# Digit_Board.net
KiCad netlist of a schematic drawn in Altium Designer
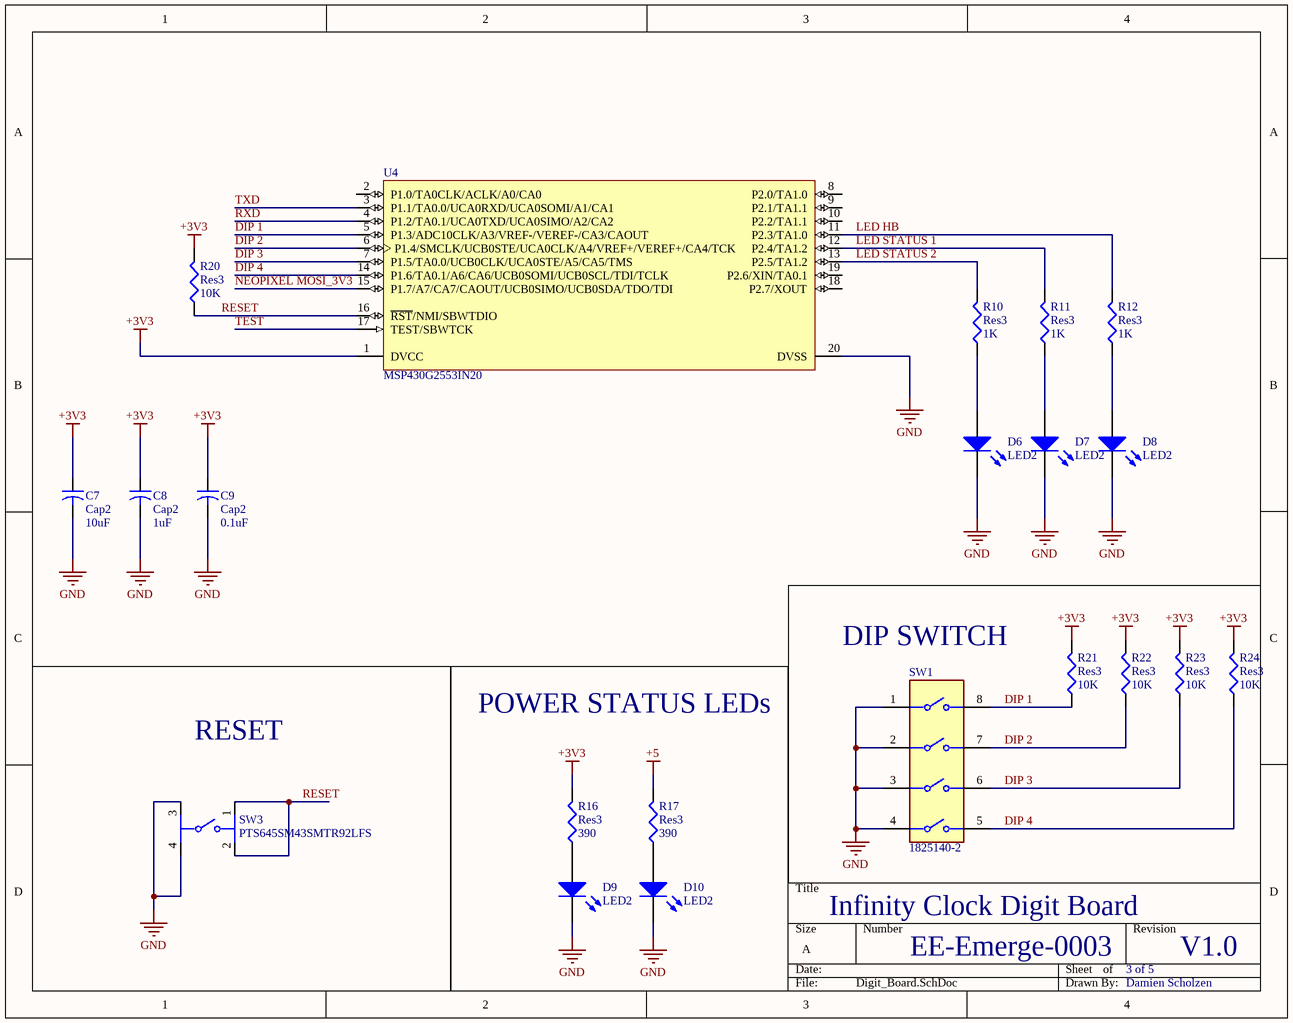
[diagram p0: Digit_Board.SchDoc]

(export (version "E")
  (design (tool "Eeschema 10.0.6"))
  (components
    (comp (ref "C7")
      (value "Cap2")
      (footprint "C0805")
      (description "Capacitor")
      (fields (field (name "ALTIUM_VALUE") "10uF") (field (name "PUBLISHER") "Altium Limited"))
      (libsource (lib "EE_Emerge_SkillsProject (1)") (part "Cap2"))
    )
    (comp (ref "C8")
      (value "Cap2")
      (footprint "C0805")
      (description "Capacitor")
      (fields (field (name "ALTIUM_VALUE") "1uF") (field (name "PUBLISHER") "Altium Limited"))
      (libsource (lib "EE_Emerge_SkillsProject (1)") (part "Cap2_1"))
    )
    (comp (ref "C9")
      (value "Cap2")
      (footprint "C0805")
      (description "Capacitor")
      (fields (field (name "ALTIUM_VALUE") "0.1uF") (field (name "PUBLISHER") "Altium Limited"))
      (libsource (lib "EE_Emerge_SkillsProject (1)") (part "Cap2_2"))
    )
    (comp (ref "D6")
      (value "LED2")
      (footprint "3.2X1.6X1.1")
      (description "Typical RED, GREEN, YELLOW, AMBER GaAs LED")
      (fields (field (name "PUBLISHER") "Altium Limited"))
      (libsource (lib "EE_Emerge_SkillsProject (1)") (part "LED2"))
    )
    (comp (ref "D7")
      (value "LED2")
      (footprint "3.2X1.6X1.1")
      (description "Typical RED, GREEN, YELLOW, AMBER GaAs LED")
      (fields (field (name "PUBLISHER") "Altium Limited"))
      (libsource (lib "EE_Emerge_SkillsProject (1)") (part "LED2"))
    )
    (comp (ref "D8")
      (value "LED2")
      (footprint "3.2X1.6X1.1")
      (description "Typical RED, GREEN, YELLOW, AMBER GaAs LED")
      (fields (field (name "PUBLISHER") "Altium Limited"))
      (libsource (lib "EE_Emerge_SkillsProject (1)") (part "LED2"))
    )
    (comp (ref "D9")
      (value "LED2")
      (footprint "3.2X1.6X1.1")
      (description "Typical RED, GREEN, YELLOW, AMBER GaAs LED")
      (fields (field (name "PUBLISHER") "Altium Limited"))
      (libsource (lib "EE_Emerge_SkillsProject (1)") (part "LED2"))
    )
    (comp (ref "D10")
      (value "LED2")
      (footprint "3.2X1.6X1.1")
      (description "Typical RED, GREEN, YELLOW, AMBER GaAs LED")
      (fields (field (name "PUBLISHER") "Altium Limited"))
      (libsource (lib "EE_Emerge_SkillsProject (1)") (part "LED2"))
    )
    (comp (ref "R10")
      (value "Res3")
      (footprint "6-0805_N")
      (description "Resistor")
      (fields (field (name "ALTIUM_VALUE") "1K") (field (name "PUBLISHER") "Altium Limited"))
      (libsource (lib "EE_Emerge_SkillsProject (1)") (part "Res3_2"))
    )
    (comp (ref "R11")
      (value "Res3")
      (footprint "6-0805_N")
      (description "Resistor")
      (fields (field (name "ALTIUM_VALUE") "1K") (field (name "PUBLISHER") "Altium Limited"))
      (libsource (lib "EE_Emerge_SkillsProject (1)") (part "Res3_2"))
    )
    (comp (ref "R12")
      (value "Res3")
      (footprint "6-0805_N")
      (description "Resistor")
      (fields (field (name "ALTIUM_VALUE") "1K") (field (name "PUBLISHER") "Altium Limited"))
      (libsource (lib "EE_Emerge_SkillsProject (1)") (part "Res3_2"))
    )
    (comp (ref "R16")
      (value "Res3")
      (footprint "6-0805_N")
      (description "Resistor")
      (fields (field (name "ALTIUM_VALUE") "390") (field (name "PUBLISHER") "Altium Limited"))
      (libsource (lib "EE_Emerge_SkillsProject (1)") (part "Res3_4"))
    )
    (comp (ref "R17")
      (value "Res3")
      (footprint "6-0805_N")
      (description "Resistor")
      (fields (field (name "ALTIUM_VALUE") "390") (field (name "PUBLISHER") "Altium Limited"))
      (libsource (lib "EE_Emerge_SkillsProject (1)") (part "Res3_4"))
    )
    (comp (ref "R20")
      (value "Res3")
      (footprint "6-0805_N")
      (description "Resistor")
      (fields (field (name "ALTIUM_VALUE") "10K") (field (name "PUBLISHER") "Altium Limited"))
      (libsource (lib "EE_Emerge_SkillsProject (1)") (part "Res3_3"))
    )
    (comp (ref "R21")
      (value "Res3")
      (footprint "6-0805_N")
      (description "Resistor")
      (fields (field (name "ALTIUM_VALUE") "10K") (field (name "PUBLISHER") "Altium Limited"))
      (libsource (lib "EE_Emerge_SkillsProject (1)") (part "Res3_3"))
    )
    (comp (ref "R22")
      (value "Res3")
      (footprint "6-0805_N")
      (description "Resistor")
      (fields (field (name "ALTIUM_VALUE") "10K") (field (name "PUBLISHER") "Altium Limited"))
      (libsource (lib "EE_Emerge_SkillsProject (1)") (part "Res3_3"))
    )
    (comp (ref "R23")
      (value "Res3")
      (footprint "6-0805_N")
      (description "Resistor")
      (fields (field (name "ALTIUM_VALUE") "10K") (field (name "PUBLISHER") "Altium Limited"))
      (libsource (lib "EE_Emerge_SkillsProject (1)") (part "Res3_3"))
    )
    (comp (ref "R24")
      (value "Res3")
      (footprint "6-0805_N")
      (description "Resistor")
      (fields (field (name "ALTIUM_VALUE") "10K") (field (name "PUBLISHER") "Altium Limited"))
      (libsource (lib "EE_Emerge_SkillsProject (1)") (part "Res3_3"))
    )
    (comp (ref "SW1")
      (value "1825140-2")
      (footprint "FP-1825140-2-MFG")
      (description "SWITCH SLIDE DIP SPST 25MA 24V")
      (libsource (lib "Altium Content Vault") (part "ee767f539d9274548732198086319ae"))
    )
    (comp (ref "SW3")
      (value "PTS645SM43SMTR92LFS")
      (footprint "FP-PTS645SM43SMTR92LFS-MFG")
      (description "SWITCH TACTILE SPST-NO 0.05A 12V")
      (libsource (lib "Altium Content Vault") (part "1adf0dd01260c80cf25a44bfd6b99ba"))
    )
    (comp (ref "U4")
      (value "MSP430G2553IN20")
      (footprint "N0020A")
      (fields (field (name "MANUFACTURER") "Texas Instruments"))
      (libsource (lib "EE_Emerge_SkillsProject (1)") (part "CMP-0365-00184-2"))
    )
  )
  (nets
    (net (code "1") (name "+3V3") (class "Default")
      (node (ref "C7") (pin "1") (pinfunction "1_1") (pintype "passive"))
      (node (ref "C8") (pin "1") (pinfunction "1_1") (pintype "passive"))
      (node (ref "C9") (pin "1") (pinfunction "1_1") (pintype "passive"))
      (node (ref "R16") (pin "2") (pinfunction "2_2") (pintype "passive"))
      (node (ref "R20") (pin "2") (pinfunction "2_2") (pintype "passive"))
      (node (ref "R21") (pin "2") (pinfunction "2_2") (pintype "passive"))
      (node (ref "R22") (pin "2") (pinfunction "2_2") (pintype "passive"))
      (node (ref "R23") (pin "2") (pinfunction "2_2") (pintype "passive"))
      (node (ref "R24") (pin "2") (pinfunction "2_2") (pintype "passive"))
      (node (ref "U4") (pin "1") (pinfunction "DVCC_1") (pintype "power_in"))
    )
    (net (code "2") (name "+5") (class "Default")
      (node (ref "R17") (pin "2") (pinfunction "2_2") (pintype "passive"))
    )
    (net (code "3") (name "/DIP 1") (class "Default")
      (node (ref "R21") (pin "1") (pinfunction "1_1") (pintype "passive"))
      (node (ref "SW1") (pin "8") (pinfunction "8_8") (pintype "passive"))
      (node (ref "U4") (pin "5") (pinfunction "P1.3/ADC10CLK/A3/VREF-/VEREF-/CA3/CAOUT_5") (pintype "bidirectional"))
    )
    (net (code "4") (name "/DIP 2") (class "Default")
      (node (ref "R22") (pin "1") (pinfunction "1_1") (pintype "passive"))
      (node (ref "SW1") (pin "7") (pinfunction "7_7") (pintype "passive"))
      (node (ref "U4") (pin "6") (pinfunction "P1.4/SMCLK/UCB0STE/UCA0CLK/A4/VREF+/VEREF+/CA4/TCK_6") (pintype "bidirectional"))
    )
    (net (code "5") (name "/DIP 3") (class "Default")
      (node (ref "R23") (pin "1") (pinfunction "1_1") (pintype "passive"))
      (node (ref "SW1") (pin "6") (pinfunction "6_6") (pintype "passive"))
      (node (ref "U4") (pin "7") (pinfunction "P1.5/TA0.0/UCB0CLK/UCA0STE/A5/CA5/TMS_7") (pintype "bidirectional"))
    )
    (net (code "6") (name "/DIP 4") (class "Default")
      (node (ref "R24") (pin "1") (pinfunction "1_1") (pintype "passive"))
      (node (ref "SW1") (pin "5") (pinfunction "5_5") (pintype "passive"))
      (node (ref "U4") (pin "14") (pinfunction "P1.6/TA0.1/A6/CA6/UCB0SOMI/UCB0SCL/TDI/TCLK_14") (pintype "bidirectional"))
    )
    (net (code "7") (name "/LED HB") (class "Default")
      (node (ref "R12") (pin "2") (pinfunction "2_2") (pintype "passive"))
      (node (ref "U4") (pin "11") (pinfunction "P2.3/TA1.0_11") (pintype "bidirectional"))
    )
    (net (code "8") (name "/LED STATUS 1") (class "Default")
      (node (ref "R11") (pin "2") (pinfunction "2_2") (pintype "passive"))
      (node (ref "U4") (pin "12") (pinfunction "P2.4/TA1.2_12") (pintype "bidirectional"))
    )
    (net (code "9") (name "/LED STATUS 2") (class "Default")
      (node (ref "R10") (pin "2") (pinfunction "2_2") (pintype "passive"))
      (node (ref "U4") (pin "13") (pinfunction "P2.5/TA1.2_13") (pintype "bidirectional"))
    )
    (net (code "10") (name "/NEOPIXEL MOSI_3V3") (class "Default")
      (node (ref "U4") (pin "15") (pinfunction "P1.7/A7/CA7/CAOUT/UCB0SIMO/UCB0SDA/TDO/TDI_15") (pintype "bidirectional"))
    )
    (net (code "11") (name "/RESET") (class "Default")
      (node (ref "R20") (pin "1") (pinfunction "1_1") (pintype "passive"))
      (node (ref "SW3") (pin "1") (pinfunction "1_1") (pintype "passive"))
      (node (ref "SW3") (pin "2") (pinfunction "2_2") (pintype "passive"))
      (node (ref "U4") (pin "16") (pinfunction "~{RST}/NMI/SBWTDIO_16") (pintype "bidirectional"))
    )
    (net (code "12") (name "/RXD") (class "Default")
      (node (ref "U4") (pin "4") (pinfunction "P1.2/TA0.1/UCA0TXD/UCA0SIMO/A2/CA2_4") (pintype "bidirectional"))
    )
    (net (code "13") (name "/TEST") (class "Default")
      (node (ref "U4") (pin "17") (pinfunction "TEST/SBWTCK_17") (pintype "input"))
    )
    (net (code "14") (name "/TXD") (class "Default")
      (node (ref "U4") (pin "3") (pinfunction "P1.1/TA0.0/UCA0RXD/UCA0SOMI/A1/CA1_3") (pintype "bidirectional"))
    )
    (net (code "15") (name "GND") (class "Default")
      (node (ref "C7") (pin "2") (pinfunction "2_2") (pintype "passive"))
      (node (ref "C8") (pin "2") (pinfunction "2_2") (pintype "passive"))
      (node (ref "C9") (pin "2") (pinfunction "2_2") (pintype "passive"))
      (node (ref "D10") (pin "2") (pinfunction "K_2") (pintype "passive"))
      (node (ref "D6") (pin "2") (pinfunction "K_2") (pintype "passive"))
      (node (ref "D7") (pin "2") (pinfunction "K_2") (pintype "passive"))
      (node (ref "D8") (pin "2") (pinfunction "K_2") (pintype "passive"))
      (node (ref "D9") (pin "2") (pinfunction "K_2") (pintype "passive"))
      (node (ref "SW1") (pin "1") (pinfunction "1_1") (pintype "passive"))
      (node (ref "SW1") (pin "2") (pinfunction "2_2") (pintype "passive"))
      (node (ref "SW1") (pin "3") (pinfunction "3_3") (pintype "passive"))
      (node (ref "SW1") (pin "4") (pinfunction "4_4") (pintype "passive"))
      (node (ref "SW3") (pin "3") (pinfunction "3_3") (pintype "passive"))
      (node (ref "SW3") (pin "4") (pinfunction "4_4") (pintype "passive"))
      (node (ref "U4") (pin "20") (pinfunction "DVSS_20") (pintype "power_in"))
    )
    (net (code "16") (name "Net-(D6-A)") (class "Default")
      (node (ref "D6") (pin "1") (pinfunction "A_1") (pintype "passive"))
      (node (ref "R10") (pin "1") (pinfunction "1_1") (pintype "passive"))
    )
    (net (code "17") (name "Net-(D7-A)") (class "Default")
      (node (ref "D7") (pin "1") (pinfunction "A_1") (pintype "passive"))
      (node (ref "R11") (pin "1") (pinfunction "1_1") (pintype "passive"))
    )
    (net (code "18") (name "Net-(D8-A)") (class "Default")
      (node (ref "D8") (pin "1") (pinfunction "A_1") (pintype "passive"))
      (node (ref "R12") (pin "1") (pinfunction "1_1") (pintype "passive"))
    )
    (net (code "19") (name "Net-(D9-A)") (class "Default")
      (node (ref "D9") (pin "1") (pinfunction "A_1") (pintype "passive"))
      (node (ref "R16") (pin "1") (pinfunction "1_1") (pintype "passive"))
    )
    (net (code "20") (name "Net-(D10-A)") (class "Default")
      (node (ref "D10") (pin "1") (pinfunction "A_1") (pintype "passive"))
      (node (ref "R17") (pin "1") (pinfunction "1_1") (pintype "passive"))
    )
    (net (code "21") (name "unconnected-(U4-P1.0{slash}TA0CLK{slash}ACLK{slash}A0{slash}CA0-Pad2)") (class "Default")
      (node (ref "U4") (pin "2") (pinfunction "P1.0/TA0CLK/ACLK/A0/CA0_2") (pintype "bidirectional"))
    )
    (net (code "22") (name "unconnected-(U4-P2.0{slash}TA1.0-Pad8)") (class "Default")
      (node (ref "U4") (pin "8") (pinfunction "P2.0/TA1.0_8") (pintype "bidirectional"))
    )
    (net (code "23") (name "unconnected-(U4-P2.1{slash}TA1.1-Pad9)") (class "Default")
      (node (ref "U4") (pin "9") (pinfunction "P2.1/TA1.1_9") (pintype "bidirectional"))
    )
    (net (code "24") (name "unconnected-(U4-P2.2{slash}TA1.1-Pad10)") (class "Default")
      (node (ref "U4") (pin "10") (pinfunction "P2.2/TA1.1_10") (pintype "bidirectional"))
    )
    (net (code "25") (name "unconnected-(U4-P2.6{slash}XIN{slash}TA0.1-Pad19)") (class "Default")
      (node (ref "U4") (pin "19") (pinfunction "P2.6/XIN/TA0.1_19") (pintype "bidirectional"))
    )
    (net (code "26") (name "unconnected-(U4-P2.7{slash}XOUT-Pad18)") (class "Default")
      (node (ref "U4") (pin "18") (pinfunction "P2.7/XOUT_18") (pintype "bidirectional"))
    )
  )
)
